# lpc810_console.net
KiCad netlist of a schematic drawn in EAGLE
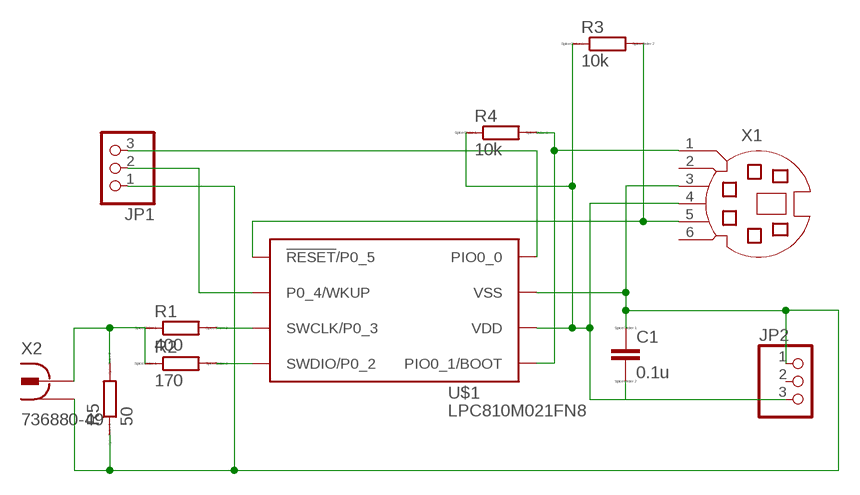
[diagram p0: schematic, sheet 1]

(export (version "E")
  (design (tool "Eeschema 10.0.6"))
  (components
    (comp (ref "C1")
      (value "0.1u")
      (footprint "eagle-import:C0603")
      (libsource (lib "eagle-import") (part "CC0603"))
    )
    (comp (ref "JP1")
      (value "PINHD-1X3")
      (footprint "eagle-import:1X03")
      (libsource (lib "eagle-import") (part "PINHD-1X3"))
    )
    (comp (ref "JP2")
      (value "PINHD-1X3")
      (footprint "eagle-import:1X03")
      (libsource (lib "eagle-import") (part "PINHD-1X3"))
    )
    (comp (ref "R1")
      (value "400")
      (footprint "eagle-import:R0603")
      (libsource (lib "eagle-import") (part "RR0603"))
    )
    (comp (ref "R2")
      (value "170")
      (footprint "eagle-import:R0603")
      (libsource (lib "eagle-import") (part "RR0603"))
    )
    (comp (ref "R3")
      (value "10k")
      (footprint "eagle-import:R0603")
      (libsource (lib "eagle-import") (part "RR0603"))
    )
    (comp (ref "R4")
      (value "10k")
      (footprint "eagle-import:R0603")
      (libsource (lib "eagle-import") (part "RR0603"))
    )
    (comp (ref "R5")
      (value "50")
      (footprint "eagle-import:R0603")
      (libsource (lib "eagle-import") (part "RR0603"))
    )
    (comp (ref "U$1")
      (value "LPC810M021FN8")
      (footprint "eagle-import:DIP8")
      (libsource (lib "eagle-import") (part "LPC810M021FN8"))
    )
    (comp (ref "X1")
      (value "MD06S")
      (footprint "eagle-import:MDIN06S")
      (libsource (lib "eagle-import") (part "MD06S"))
    )
    (comp (ref "X2")
      (value "736880-49")
      (footprint "eagle-import:736880-49")
      (libsource (lib "eagle-import") (part "736880-49"))
    )
  )
  (nets
    (net (code "1") (name "Net-(R1-Pad1)") (class "Default")
      (node (ref "R1") (pin "1") (pinfunction "1_1") (pintype "passive"))
      (node (ref "R2") (pin "1") (pinfunction "1_1") (pintype "passive"))
      (node (ref "R5") (pin "2") (pinfunction "2_2") (pintype "passive"))
      (node (ref "X2") (pin "2") (pinfunction "2_2") (pintype "passive"))
    )
    (net (code "2") (name "Net-(U$1-P0_4{slash}WKUP)") (class "Default")
      (node (ref "JP1") (pin "2") (pinfunction "2_2") (pintype "passive"))
      (node (ref "U$1") (pin "P$2") (pinfunction "P0_4/WKUP_P$2") (pintype "bidirectional"))
    )
    (net (code "3") (name "Net-(U$1-PIO0_0)") (class "Default")
      (node (ref "JP1") (pin "3") (pinfunction "3_3") (pintype "passive"))
      (node (ref "U$1") (pin "P$8") (pinfunction "PIO0_0_P$8") (pintype "bidirectional"))
    )
    (net (code "4") (name "Net-(U$1-PIO0_1{slash}BOOT)") (class "Default")
      (node (ref "R4") (pin "2") (pinfunction "2_2") (pintype "passive"))
      (node (ref "U$1") (pin "P$5") (pinfunction "PIO0_1/BOOT_P$5") (pintype "bidirectional"))
      (node (ref "X1") (pin "1") (pinfunction "1_1") (pintype "passive"))
    )
    (net (code "5") (name "Net-(U$1-SWCLK{slash}P0_3)") (class "Default")
      (node (ref "R1") (pin "2") (pinfunction "2_2") (pintype "passive"))
      (node (ref "U$1") (pin "P$3") (pinfunction "SWCLK/P0_3_P$3") (pintype "bidirectional"))
    )
    (net (code "6") (name "Net-(U$1-SWDIO{slash}P0_2)") (class "Default")
      (node (ref "R2") (pin "2") (pinfunction "2_2") (pintype "passive"))
      (node (ref "U$1") (pin "P$4") (pinfunction "SWDIO/P0_2_P$4") (pintype "bidirectional"))
    )
    (net (code "7") (name "Net-(U$1-VDD)") (class "Default")
      (node (ref "C1") (pin "2") (pinfunction "2_2") (pintype "passive"))
      (node (ref "JP2") (pin "3") (pinfunction "3_3") (pintype "passive"))
      (node (ref "R3") (pin "1") (pinfunction "1_1") (pintype "passive"))
      (node (ref "R4") (pin "1") (pinfunction "1_1") (pintype "passive"))
      (node (ref "U$1") (pin "P$6") (pinfunction "VDD_P$6") (pintype "bidirectional"))
      (node (ref "X1") (pin "4") (pinfunction "4_4") (pintype "passive"))
    )
    (net (code "8") (name "Net-(U$1-VSS)") (class "Default")
      (node (ref "C1") (pin "1") (pinfunction "1_1") (pintype "passive"))
      (node (ref "JP1") (pin "1") (pinfunction "1_1") (pintype "passive"))
      (node (ref "JP2") (pin "1") (pinfunction "1_1") (pintype "passive"))
      (node (ref "R5") (pin "1") (pinfunction "1_1") (pintype "passive"))
      (node (ref "U$1") (pin "P$7") (pinfunction "VSS_P$7") (pintype "bidirectional"))
      (node (ref "X1") (pin "3") (pinfunction "3_3") (pintype "passive"))
      (node (ref "X2") (pin "1") (pinfunction "1_1") (pintype "passive"))
      (node (ref "X2") (pin "1@1") (pinfunction "1_1@1") (pintype "passive"))
      (node (ref "X2") (pin "1@2") (pinfunction "1_1@2") (pintype "passive"))
    )
    (net (code "9") (name "Net-(U$1-~{RESET}{slash}P0_5)") (class "Default")
      (node (ref "R3") (pin "2") (pinfunction "2_2") (pintype "passive"))
      (node (ref "U$1") (pin "P$1") (pinfunction "~{RESET}/P0_5_P$1") (pintype "bidirectional"))
      (node (ref "X1") (pin "5") (pinfunction "5_5") (pintype "passive"))
    )
    (net (code "10") (name "unconnected-(JP2-Pad2)") (class "Default")
      (node (ref "JP2") (pin "2") (pinfunction "2_2") (pintype "passive"))
    )
    (net (code "11") (name "unconnected-(X1-Pad2)") (class "Default")
      (node (ref "X1") (pin "2") (pinfunction "2_2") (pintype "passive"))
    )
    (net (code "12") (name "unconnected-(X1-Pad6)") (class "Default")
      (node (ref "X1") (pin "6") (pinfunction "6_6") (pintype "passive"))
    )
  )
)
